# COM_R_UPDATED.net
KiCad netlist of a schematic drawn in EAGLE
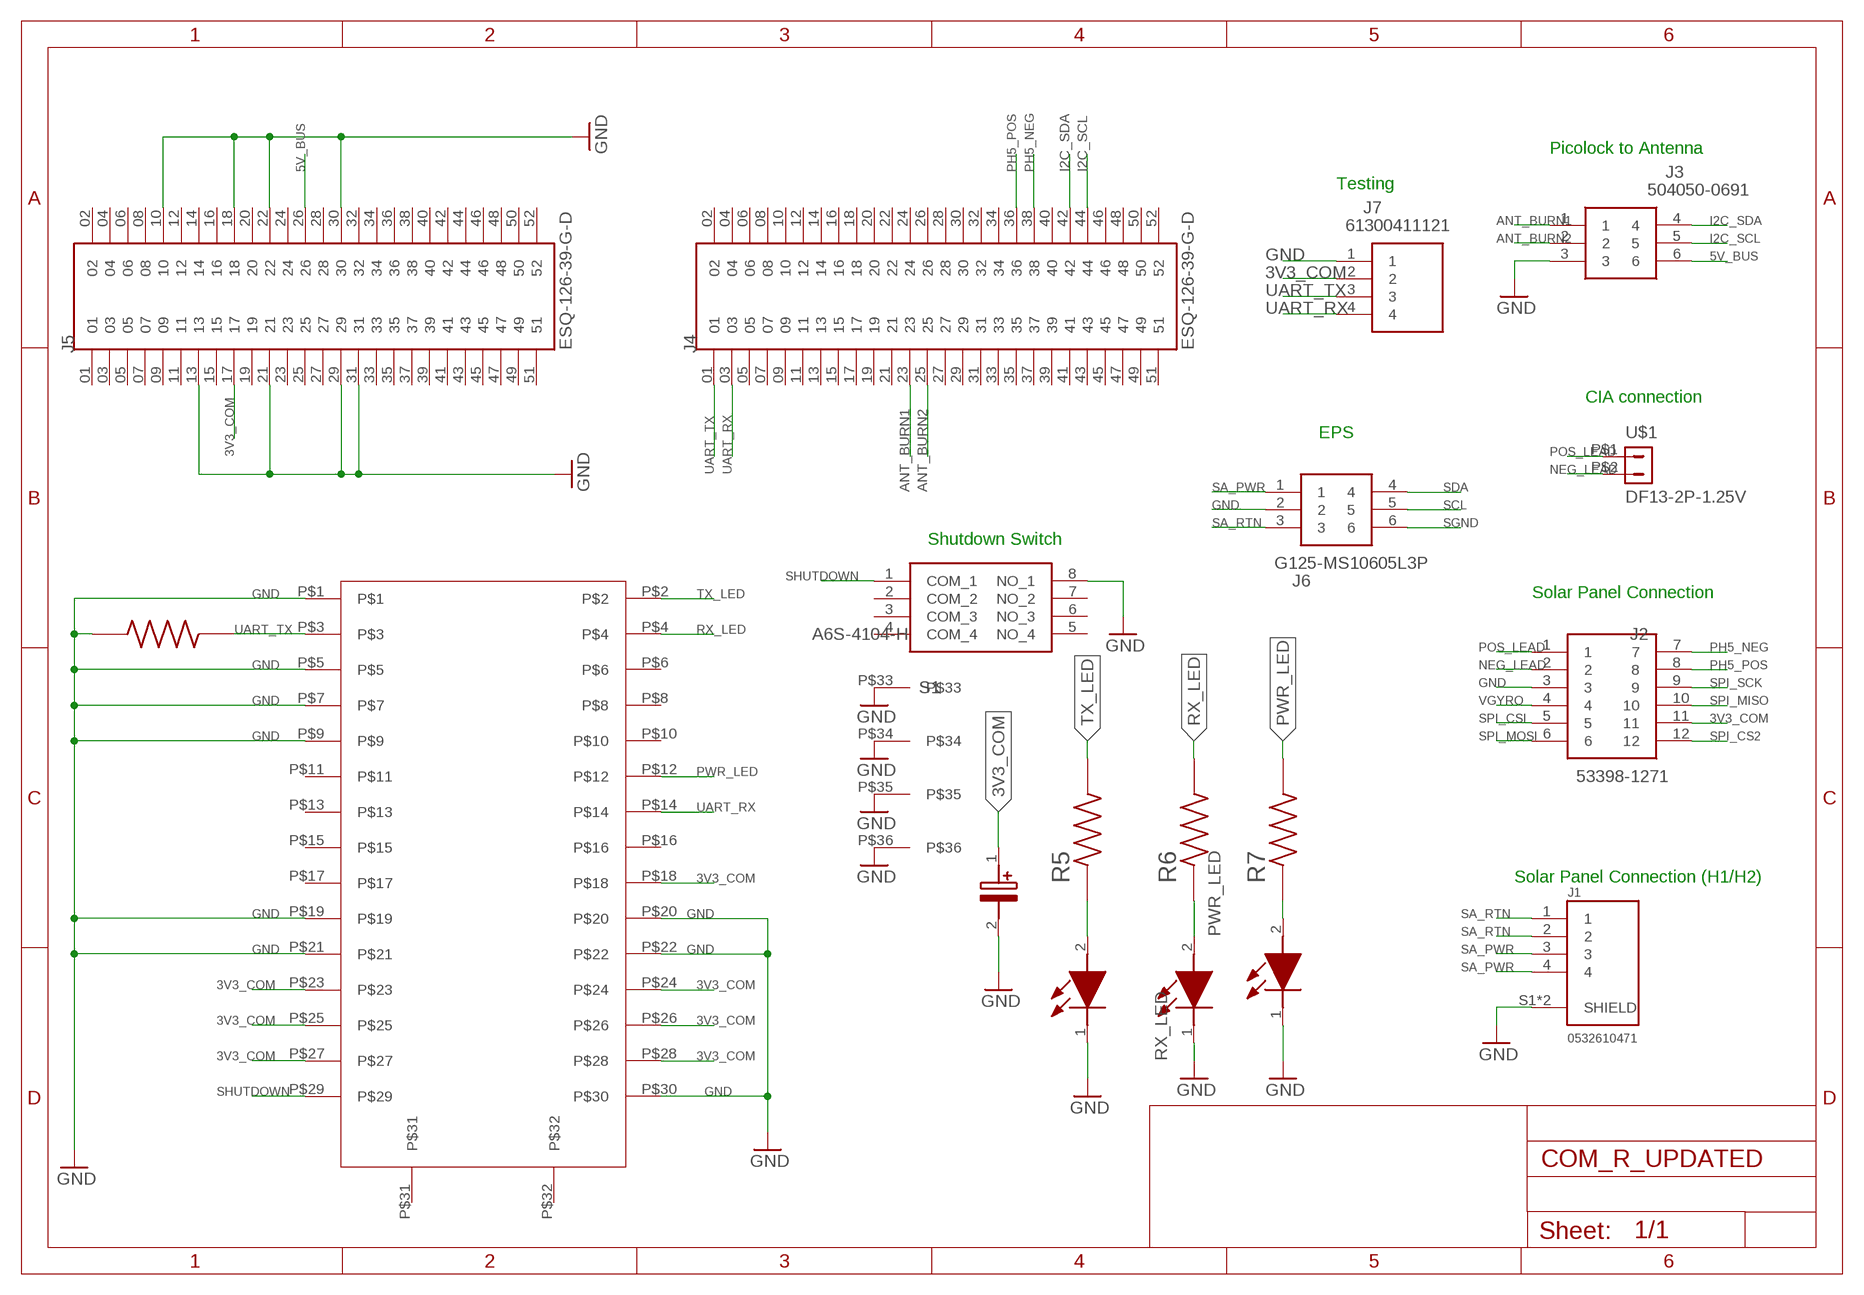
[diagram p0: schematic, sheet 1]

(export (version "E")
  (design (tool "Eeschema 10.0.6"))
  (components
    (comp (ref "C2")
      (value "293D106X0010A2TE3")
      (footprint "eagle-import:CAPPM3216X180N")
      (fields (field (name "MOUSER_PART_NUMBER") "74-293D106X0010A2TE3"))
      (libsource (lib "eagle-import") (part "293D106X0010A2TE3"))
    )
    (comp (ref "J1")
      (value "0532610471")
      (footprint "eagle-import:MOLEX_0532610471")
      (fields (field (name "MF") "Molex"))
      (libsource (lib "eagle-import") (part "0532610471"))
    )
    (comp (ref "J2")
      (value "53398-1271")
      (footprint "eagle-import:53398-1271")
      (fields (field (name "MOUSER_PART_NUMBER") "538-53398-1271"))
      (libsource (lib "eagle-import") (part "53398-1271"))
    )
    (comp (ref "J3")
      (value "504050-0691")
      (footprint "eagle-import:504050-0691_2")
      (fields (field (name "MOUSER_PART_NUMBER") "538-504050-0691"))
      (libsource (lib "eagle-import") (part "504050-0691"))
    )
    (comp (ref "J4")
      (value "ESQ-126-39-G-D")
      (footprint "eagle-import:SAMTEC_ESQ-126-39-G-D")
      (fields (field (name "MF") "Samtec"))
      (libsource (lib "eagle-import") (part "ESQ-126-39-G-D"))
    )
    (comp (ref "J5")
      (value "ESQ-126-39-G-D")
      (footprint "eagle-import:SAMTEC_ESQ-126-39-G-D")
      (fields (field (name "MF") "Samtec"))
      (libsource (lib "eagle-import") (part "ESQ-126-39-G-D"))
    )
    (comp (ref "J6")
      (value "G125-MS10605L3P")
      (footprint "eagle-import:G125-MS10605L3P")
      (fields (field (name "MOUSER_PART_NUMBER") "855-G125-MS10605L3P"))
      (libsource (lib "eagle-import") (part "G125-MS10605L3P"))
    )
    (comp (ref "J7")
      (value "61300411121")
      (footprint "eagle-import:HDRV4W95P0X254_1X4_1016X254X85")
      (fields (field (name "MOUSER_PART_NUMBER") "710-61300411121"))
      (libsource (lib "eagle-import") (part "61300411121"))
    )
    (comp (ref "PWR_LED")
      (value "HSMQ-C170-T0000")
      (footprint "eagle-import:LEDC2012X90N")
      (fields (field (name "MOUSER_PART_NUMBER") "630-HSMQ-C170-T0000"))
      (libsource (lib "eagle-import") (part "HSMQ-C170-T0000"))
    )
    (comp (ref "R3")
      (value "TNPW080510K0BETY")
      (footprint "eagle-import:RESC2012X55N")
      (fields (field (name "DIGI-KEY_PART_NUMBER") "541-3913-1-ND") (field (name "MF") "Vishay"))
      (libsource (lib "eagle-import") (part "TNPW080510K0BETY"))
    )
    (comp (ref "R5")
      (value "Y40621K00000Q0R")
      (footprint "eagle-import:RESC2012X64N")
      (fields (field (name "DIGI-KEY_PART_NUMBER") "Y4062-1.0KACT-ND") (field (name "MF") "Vishay"))
      (libsource (lib "eagle-import") (part "Y40621K00000Q0R"))
    )
    (comp (ref "R6")
      (value "Y40621K00000Q0R")
      (footprint "eagle-import:RESC2012X64N")
      (fields (field (name "DIGI-KEY_PART_NUMBER") "Y4062-1.0KACT-ND") (field (name "MF") "Vishay"))
      (libsource (lib "eagle-import") (part "Y40621K00000Q0R"))
    )
    (comp (ref "R7")
      (value "Y40621K00000Q0R")
      (footprint "eagle-import:RESC2012X64N")
      (fields (field (name "DIGI-KEY_PART_NUMBER") "Y4062-1.0KACT-ND") (field (name "MF") "Vishay"))
      (libsource (lib "eagle-import") (part "Y40621K00000Q0R"))
    )
    (comp (ref "RX_LED")
      (value "HSMQ-C170-T0000")
      (footprint "eagle-import:LEDC2012X90N")
      (fields (field (name "MOUSER_PART_NUMBER") "630-HSMQ-C170-T0000"))
      (libsource (lib "eagle-import") (part "HSMQ-C170-T0000"))
    )
    (comp (ref "S1")
      (value "A6S-4104-H")
      (footprint "eagle-import:A6S4104H")
      (fields (field (name "MOUSER_PART_NUMBER") "653-A6S-4104-H"))
      (libsource (lib "eagle-import") (part "A6S-4104-H"))
    )
    (comp (ref "TX_LED")
      (value "HSMQ-C170-T0000")
      (footprint "eagle-import:LEDC2012X90N")
      (fields (field (name "MOUSER_PART_NUMBER") "630-HSMQ-C170-T0000"))
      (libsource (lib "eagle-import") (part "HSMQ-C170-T0000"))
    )
    (comp (ref "U$1")
      (value "DF13-2P-1.25V")
      (footprint "eagle-import:DF13C-2P-1.25V")
      (libsource (lib "eagle-import") (part "DF13-2P-1.25V"))
    )
    (comp (ref "U$3")
      (value "KYOCERA_5046_30PIN")
      (footprint "eagle-import:KYOCERA_5046_30PIN")
      (libsource (lib "eagle-import") (part "KYOCERA_5046_30PIN"))
    )
  )
  (nets
    (net (code "1") (name "/5V_BUS") (class "Default")
      (node (ref "J3") (pin "6") (pinfunction "6_6") (pintype "bidirectional"))
      (node (ref "J5") (pin "26") (pinfunction "26_26") (pintype "passive"))
    )
    (net (code "2") (name "/ANT_BURN1") (class "Default")
      (node (ref "J3") (pin "1") (pinfunction "1_1") (pintype "bidirectional"))
      (node (ref "J4") (pin "23") (pinfunction "23_23") (pintype "passive"))
    )
    (net (code "3") (name "/ANT_BURN2") (class "Default")
      (node (ref "J3") (pin "2") (pinfunction "2_2") (pintype "bidirectional"))
      (node (ref "J4") (pin "25") (pinfunction "25_25") (pintype "passive"))
    )
    (net (code "4") (name "/I2C_SCL") (class "Default")
      (node (ref "J3") (pin "5") (pinfunction "5_5") (pintype "bidirectional"))
      (node (ref "J4") (pin "44") (pinfunction "44_44") (pintype "passive"))
    )
    (net (code "5") (name "/I2C_SDA") (class "Default")
      (node (ref "J3") (pin "4") (pinfunction "4_4") (pintype "bidirectional"))
      (node (ref "J4") (pin "42") (pinfunction "42_42") (pintype "passive"))
    )
    (net (code "6") (name "/NEG_LEAD") (class "Default")
      (node (ref "J2") (pin "2") (pinfunction "2_2") (pintype "bidirectional"))
      (node (ref "U$1") (pin "P$2") (pinfunction "2_P$2") (pintype "passive"))
    )
    (net (code "7") (name "/PH5_NEG") (class "Default")
      (node (ref "J2") (pin "7") (pinfunction "7_7") (pintype "bidirectional"))
      (node (ref "J4") (pin "38") (pinfunction "38_38") (pintype "passive"))
    )
    (net (code "8") (name "/PH5_POS") (class "Default")
      (node (ref "J2") (pin "8") (pinfunction "8_8") (pintype "bidirectional"))
      (node (ref "J4") (pin "36") (pinfunction "36_36") (pintype "passive"))
    )
    (net (code "9") (name "/POS_LEAD") (class "Default")
      (node (ref "J2") (pin "1") (pinfunction "1_1") (pintype "bidirectional"))
      (node (ref "U$1") (pin "P$1") (pinfunction "1_P$1") (pintype "passive"))
    )
    (net (code "10") (name "/SA_PWR") (class "Default")
      (node (ref "J1") (pin "3") (pinfunction "3_3") (pintype "passive"))
      (node (ref "J1") (pin "4") (pinfunction "4_4") (pintype "passive"))
      (node (ref "J6") (pin "1") (pinfunction "1_1") (pintype "bidirectional"))
    )
    (net (code "11") (name "/SA_RTN") (class "Default")
      (node (ref "J1") (pin "1") (pinfunction "1_1") (pintype "passive"))
      (node (ref "J1") (pin "2") (pinfunction "2_2") (pintype "passive"))
      (node (ref "J6") (pin "3") (pinfunction "3_3") (pintype "bidirectional"))
    )
    (net (code "12") (name "/SCL") (class "Default")
      (node (ref "J6") (pin "5") (pinfunction "5_5") (pintype "bidirectional"))
    )
    (net (code "13") (name "/SDA") (class "Default")
      (node (ref "J6") (pin "4") (pinfunction "4_4") (pintype "bidirectional"))
    )
    (net (code "14") (name "/SGND") (class "Default")
      (node (ref "J6") (pin "6") (pinfunction "6_6") (pintype "bidirectional"))
    )
    (net (code "15") (name "/SHUTDOWN") (class "Default")
      (node (ref "S1") (pin "1") (pinfunction "COM_1_1") (pintype "bidirectional"))
      (node (ref "U$3") (pin "P$29") (pinfunction "P$29_P$29") (pintype "bidirectional"))
    )
    (net (code "16") (name "/SPI_CS2") (class "Default")
      (node (ref "J2") (pin "12") (pinfunction "12_12") (pintype "bidirectional"))
    )
    (net (code "17") (name "/SPI_CSI") (class "Default")
      (node (ref "J2") (pin "5") (pinfunction "5_5") (pintype "bidirectional"))
    )
    (net (code "18") (name "/SPI_MISO") (class "Default")
      (node (ref "J2") (pin "10") (pinfunction "10_10") (pintype "bidirectional"))
    )
    (net (code "19") (name "/SPI_MOSI") (class "Default")
      (node (ref "J2") (pin "6") (pinfunction "6_6") (pintype "bidirectional"))
    )
    (net (code "20") (name "/SPI_SCK") (class "Default")
      (node (ref "J2") (pin "9") (pinfunction "9_9") (pintype "bidirectional"))
    )
    (net (code "21") (name "/UART_RX") (class "Default")
      (node (ref "J4") (pin "03") (pinfunction "03_03") (pintype "passive"))
      (node (ref "J7") (pin "4") (pinfunction "4_4") (pintype "bidirectional"))
      (node (ref "U$3") (pin "P$14") (pinfunction "P$14_P$14") (pintype "bidirectional"))
    )
    (net (code "22") (name "/UART_TX") (class "Default")
      (node (ref "J4") (pin "01") (pinfunction "01_01") (pintype "passive"))
      (node (ref "J7") (pin "3") (pinfunction "3_3") (pintype "bidirectional"))
      (node (ref "R3") (pin "2") (pinfunction "2_2") (pintype "passive"))
      (node (ref "U$3") (pin "P$3") (pinfunction "P$3_P$3") (pintype "bidirectional"))
    )
    (net (code "23") (name "/VGYRO") (class "Default")
      (node (ref "J2") (pin "4") (pinfunction "4_4") (pintype "bidirectional"))
    )
    (net (code "24") (name "3V3_COM") (class "Default")
      (node (ref "C2") (pin "1") (pinfunction "+_1") (pintype "bidirectional"))
      (node (ref "J2") (pin "11") (pinfunction "11_11") (pintype "bidirectional"))
      (node (ref "J5") (pin "17") (pinfunction "17_17") (pintype "passive"))
      (node (ref "J7") (pin "2") (pinfunction "2_2") (pintype "bidirectional"))
      (node (ref "U$3") (pin "P$18") (pinfunction "P$18_P$18") (pintype "bidirectional"))
      (node (ref "U$3") (pin "P$23") (pinfunction "P$23_P$23") (pintype "bidirectional"))
      (node (ref "U$3") (pin "P$24") (pinfunction "P$24_P$24") (pintype "bidirectional"))
      (node (ref "U$3") (pin "P$25") (pinfunction "P$25_P$25") (pintype "bidirectional"))
      (node (ref "U$3") (pin "P$26") (pinfunction "P$26_P$26") (pintype "bidirectional"))
      (node (ref "U$3") (pin "P$27") (pinfunction "P$27_P$27") (pintype "bidirectional"))
      (node (ref "U$3") (pin "P$28") (pinfunction "P$28_P$28") (pintype "bidirectional"))
    )
    (net (code "25") (name "GND") (class "Default")
      (node (ref "C2") (pin "2") (pinfunction "-_2") (pintype "bidirectional"))
      (node (ref "J1") (pin "S1") (pinfunction "SHIELD_S1") (pintype "passive"))
      (node (ref "J1") (pin "S2") (pinfunction "SHIELD_S2") (pintype "passive"))
      (node (ref "J2") (pin "3") (pinfunction "3_3") (pintype "bidirectional"))
      (node (ref "J3") (pin "3") (pinfunction "3_3") (pintype "bidirectional"))
      (node (ref "J5") (pin "10") (pinfunction "10_10") (pintype "passive"))
      (node (ref "J5") (pin "13") (pinfunction "13_13") (pintype "passive"))
      (node (ref "J5") (pin "18") (pinfunction "18_18") (pintype "passive"))
      (node (ref "J5") (pin "21") (pinfunction "21_21") (pintype "passive"))
      (node (ref "J5") (pin "22") (pinfunction "22_22") (pintype "passive"))
      (node (ref "J5") (pin "29") (pinfunction "29_29") (pintype "passive"))
      (node (ref "J5") (pin "30") (pinfunction "30_30") (pintype "passive"))
      (node (ref "J5") (pin "31") (pinfunction "31_31") (pintype "passive"))
      (node (ref "J6") (pin "2") (pinfunction "2_2") (pintype "bidirectional"))
      (node (ref "J7") (pin "1") (pinfunction "1_1") (pintype "bidirectional"))
      (node (ref "PWR_LED") (pin "1") (pinfunction "K_1") (pintype "bidirectional"))
      (node (ref "R3") (pin "1") (pinfunction "1_1") (pintype "passive"))
      (node (ref "RX_LED") (pin "1") (pinfunction "K_1") (pintype "bidirectional"))
      (node (ref "S1") (pin "8") (pinfunction "NO_1_8") (pintype "bidirectional"))
      (node (ref "TX_LED") (pin "1") (pinfunction "K_1") (pintype "bidirectional"))
      (node (ref "U$3") (pin "P$1") (pinfunction "P$1_P$1") (pintype "bidirectional"))
      (node (ref "U$3") (pin "P$19") (pinfunction "P$19_P$19") (pintype "bidirectional"))
      (node (ref "U$3") (pin "P$20") (pinfunction "P$20_P$20") (pintype "bidirectional"))
      (node (ref "U$3") (pin "P$21") (pinfunction "P$21_P$21") (pintype "bidirectional"))
      (node (ref "U$3") (pin "P$22") (pinfunction "P$22_P$22") (pintype "bidirectional"))
      (node (ref "U$3") (pin "P$30") (pinfunction "P$30_P$30") (pintype "bidirectional"))
      (node (ref "U$3") (pin "P$33") (pinfunction "P$33_P$33") (pintype "bidirectional"))
      (node (ref "U$3") (pin "P$34") (pinfunction "P$34_P$34") (pintype "bidirectional"))
      (node (ref "U$3") (pin "P$35") (pinfunction "P$35_P$35") (pintype "bidirectional"))
      (node (ref "U$3") (pin "P$36") (pinfunction "P$36_P$36") (pintype "bidirectional"))
      (node (ref "U$3") (pin "P$5") (pinfunction "P$5_P$5") (pintype "bidirectional"))
      (node (ref "U$3") (pin "P$7") (pinfunction "P$7_P$7") (pintype "bidirectional"))
      (node (ref "U$3") (pin "P$9") (pinfunction "P$9_P$9") (pintype "bidirectional"))
    )
    (net (code "26") (name "Net-(PWR_LED-A)") (class "Default")
      (node (ref "PWR_LED") (pin "2") (pinfunction "A_2") (pintype "bidirectional"))
      (node (ref "R7") (pin "1") (pinfunction "1_1") (pintype "passive"))
    )
    (net (code "27") (name "Net-(RX_LED-A)") (class "Default")
      (node (ref "R6") (pin "1") (pinfunction "1_1") (pintype "passive"))
      (node (ref "RX_LED") (pin "2") (pinfunction "A_2") (pintype "bidirectional"))
    )
    (net (code "28") (name "Net-(TX_LED-A)") (class "Default")
      (node (ref "R5") (pin "1") (pinfunction "1_1") (pintype "passive"))
      (node (ref "TX_LED") (pin "2") (pinfunction "A_2") (pintype "bidirectional"))
    )
    (net (code "29") (name "PWR_LED") (class "Default")
      (node (ref "R7") (pin "2") (pinfunction "2_2") (pintype "passive"))
      (node (ref "U$3") (pin "P$12") (pinfunction "P$12_P$12") (pintype "bidirectional"))
    )
    (net (code "30") (name "RX_LED") (class "Default")
      (node (ref "R6") (pin "2") (pinfunction "2_2") (pintype "passive"))
      (node (ref "U$3") (pin "P$4") (pinfunction "P$4_P$4") (pintype "bidirectional"))
    )
    (net (code "31") (name "TX_LED") (class "Default")
      (node (ref "R5") (pin "2") (pinfunction "2_2") (pintype "passive"))
      (node (ref "U$3") (pin "P$2") (pinfunction "P$2_P$2") (pintype "bidirectional"))
    )
    (net (code "32") (name "unconnected-(J4-Pad02)") (class "Default")
      (node (ref "J4") (pin "02") (pinfunction "02_02") (pintype "passive"))
    )
    (net (code "33") (name "unconnected-(J4-Pad04)") (class "Default")
      (node (ref "J4") (pin "04") (pinfunction "04_04") (pintype "passive"))
    )
    (net (code "34") (name "unconnected-(J4-Pad05)") (class "Default")
      (node (ref "J4") (pin "05") (pinfunction "05_05") (pintype "passive"))
    )
    (net (code "35") (name "unconnected-(J4-Pad06)") (class "Default")
      (node (ref "J4") (pin "06") (pinfunction "06_06") (pintype "passive"))
    )
    (net (code "36") (name "unconnected-(J4-Pad07)") (class "Default")
      (node (ref "J4") (pin "07") (pinfunction "07_07") (pintype "passive"))
    )
    (net (code "37") (name "unconnected-(J4-Pad08)") (class "Default")
      (node (ref "J4") (pin "08") (pinfunction "08_08") (pintype "passive"))
    )
    (net (code "38") (name "unconnected-(J4-Pad09)") (class "Default")
      (node (ref "J4") (pin "09") (pinfunction "09_09") (pintype "passive"))
    )
    (net (code "39") (name "unconnected-(J4-Pad10)") (class "Default")
      (node (ref "J4") (pin "10") (pinfunction "10_10") (pintype "passive"))
    )
    (net (code "40") (name "unconnected-(J4-Pad11)") (class "Default")
      (node (ref "J4") (pin "11") (pinfunction "11_11") (pintype "passive"))
    )
    (net (code "41") (name "unconnected-(J4-Pad12)") (class "Default")
      (node (ref "J4") (pin "12") (pinfunction "12_12") (pintype "passive"))
    )
    (net (code "42") (name "unconnected-(J4-Pad13)") (class "Default")
      (node (ref "J4") (pin "13") (pinfunction "13_13") (pintype "passive"))
    )
    (net (code "43") (name "unconnected-(J4-Pad14)") (class "Default")
      (node (ref "J4") (pin "14") (pinfunction "14_14") (pintype "passive"))
    )
    (net (code "44") (name "unconnected-(J4-Pad15)") (class "Default")
      (node (ref "J4") (pin "15") (pinfunction "15_15") (pintype "passive"))
    )
    (net (code "45") (name "unconnected-(J4-Pad16)") (class "Default")
      (node (ref "J4") (pin "16") (pinfunction "16_16") (pintype "passive"))
    )
    (net (code "46") (name "unconnected-(J4-Pad17)") (class "Default")
      (node (ref "J4") (pin "17") (pinfunction "17_17") (pintype "passive"))
    )
    (net (code "47") (name "unconnected-(J4-Pad18)") (class "Default")
      (node (ref "J4") (pin "18") (pinfunction "18_18") (pintype "passive"))
    )
    (net (code "48") (name "unconnected-(J4-Pad19)") (class "Default")
      (node (ref "J4") (pin "19") (pinfunction "19_19") (pintype "passive"))
    )
    (net (code "49") (name "unconnected-(J4-Pad20)") (class "Default")
      (node (ref "J4") (pin "20") (pinfunction "20_20") (pintype "passive"))
    )
    (net (code "50") (name "unconnected-(J4-Pad21)") (class "Default")
      (node (ref "J4") (pin "21") (pinfunction "21_21") (pintype "passive"))
    )
    (net (code "51") (name "unconnected-(J4-Pad22)") (class "Default")
      (node (ref "J4") (pin "22") (pinfunction "22_22") (pintype "passive"))
    )
    (net (code "52") (name "unconnected-(J4-Pad24)") (class "Default")
      (node (ref "J4") (pin "24") (pinfunction "24_24") (pintype "passive"))
    )
    (net (code "53") (name "unconnected-(J4-Pad26)") (class "Default")
      (node (ref "J4") (pin "26") (pinfunction "26_26") (pintype "passive"))
    )
    (net (code "54") (name "unconnected-(J4-Pad27)") (class "Default")
      (node (ref "J4") (pin "27") (pinfunction "27_27") (pintype "passive"))
    )
    (net (code "55") (name "unconnected-(J4-Pad28)") (class "Default")
      (node (ref "J4") (pin "28") (pinfunction "28_28") (pintype "passive"))
    )
    (net (code "56") (name "unconnected-(J4-Pad29)") (class "Default")
      (node (ref "J4") (pin "29") (pinfunction "29_29") (pintype "passive"))
    )
    (net (code "57") (name "unconnected-(J4-Pad30)") (class "Default")
      (node (ref "J4") (pin "30") (pinfunction "30_30") (pintype "passive"))
    )
    (net (code "58") (name "unconnected-(J4-Pad31)") (class "Default")
      (node (ref "J4") (pin "31") (pinfunction "31_31") (pintype "passive"))
    )
    (net (code "59") (name "unconnected-(J4-Pad32)") (class "Default")
      (node (ref "J4") (pin "32") (pinfunction "32_32") (pintype "passive"))
    )
    (net (code "60") (name "unconnected-(J4-Pad33)") (class "Default")
      (node (ref "J4") (pin "33") (pinfunction "33_33") (pintype "passive"))
    )
    (net (code "61") (name "unconnected-(J4-Pad34)") (class "Default")
      (node (ref "J4") (pin "34") (pinfunction "34_34") (pintype "passive"))
    )
    (net (code "62") (name "unconnected-(J4-Pad35)") (class "Default")
      (node (ref "J4") (pin "35") (pinfunction "35_35") (pintype "passive"))
    )
    (net (code "63") (name "unconnected-(J4-Pad37)") (class "Default")
      (node (ref "J4") (pin "37") (pinfunction "37_37") (pintype "passive"))
    )
    (net (code "64") (name "unconnected-(J4-Pad39)") (class "Default")
      (node (ref "J4") (pin "39") (pinfunction "39_39") (pintype "passive"))
    )
    (net (code "65") (name "unconnected-(J4-Pad40)") (class "Default")
      (node (ref "J4") (pin "40") (pinfunction "40_40") (pintype "passive"))
    )
    (net (code "66") (name "unconnected-(J4-Pad41)") (class "Default")
      (node (ref "J4") (pin "41") (pinfunction "41_41") (pintype "passive"))
    )
    (net (code "67") (name "unconnected-(J4-Pad43)") (class "Default")
      (node (ref "J4") (pin "43") (pinfunction "43_43") (pintype "passive"))
    )
    (net (code "68") (name "unconnected-(J4-Pad45)") (class "Default")
      (node (ref "J4") (pin "45") (pinfunction "45_45") (pintype "passive"))
    )
    (net (code "69") (name "unconnected-(J4-Pad46)") (class "Default")
      (node (ref "J4") (pin "46") (pinfunction "46_46") (pintype "passive"))
    )
    (net (code "70") (name "unconnected-(J4-Pad47)") (class "Default")
      (node (ref "J4") (pin "47") (pinfunction "47_47") (pintype "passive"))
    )
    (net (code "71") (name "unconnected-(J4-Pad48)") (class "Default")
      (node (ref "J4") (pin "48") (pinfunction "48_48") (pintype "passive"))
    )
    (net (code "72") (name "unconnected-(J4-Pad49)") (class "Default")
      (node (ref "J4") (pin "49") (pinfunction "49_49") (pintype "passive"))
    )
    (net (code "73") (name "unconnected-(J4-Pad50)") (class "Default")
      (node (ref "J4") (pin "50") (pinfunction "50_50") (pintype "passive"))
    )
    (net (code "74") (name "unconnected-(J4-Pad51)") (class "Default")
      (node (ref "J4") (pin "51") (pinfunction "51_51") (pintype "passive"))
    )
    (net (code "75") (name "unconnected-(J4-Pad52)") (class "Default")
      (node (ref "J4") (pin "52") (pinfunction "52_52") (pintype "passive"))
    )
    (net (code "76") (name "unconnected-(J5-Pad01)") (class "Default")
      (node (ref "J5") (pin "01") (pinfunction "01_01") (pintype "passive"))
    )
    (net (code "77") (name "unconnected-(J5-Pad02)") (class "Default")
      (node (ref "J5") (pin "02") (pinfunction "02_02") (pintype "passive"))
    )
    (net (code "78") (name "unconnected-(J5-Pad03)") (class "Default")
      (node (ref "J5") (pin "03") (pinfunction "03_03") (pintype "passive"))
    )
    (net (code "79") (name "unconnected-(J5-Pad04)") (class "Default")
      (node (ref "J5") (pin "04") (pinfunction "04_04") (pintype "passive"))
    )
    (net (code "80") (name "unconnected-(J5-Pad05)") (class "Default")
      (node (ref "J5") (pin "05") (pinfunction "05_05") (pintype "passive"))
    )
    (net (code "81") (name "unconnected-(J5-Pad06)") (class "Default")
      (node (ref "J5") (pin "06") (pinfunction "06_06") (pintype "passive"))
    )
    (net (code "82") (name "unconnected-(J5-Pad07)") (class "Default")
      (node (ref "J5") (pin "07") (pinfunction "07_07") (pintype "passive"))
    )
    (net (code "83") (name "unconnected-(J5-Pad08)") (class "Default")
      (node (ref "J5") (pin "08") (pinfunction "08_08") (pintype "passive"))
    )
    (net (code "84") (name "unconnected-(J5-Pad09)") (class "Default")
      (node (ref "J5") (pin "09") (pinfunction "09_09") (pintype "passive"))
    )
    (net (code "85") (name "unconnected-(J5-Pad11)") (class "Default")
      (node (ref "J5") (pin "11") (pinfunction "11_11") (pintype "passive"))
    )
    (net (code "86") (name "unconnected-(J5-Pad12)") (class "Default")
      (node (ref "J5") (pin "12") (pinfunction "12_12") (pintype "passive"))
    )
    (net (code "87") (name "unconnected-(J5-Pad14)") (class "Default")
      (node (ref "J5") (pin "14") (pinfunction "14_14") (pintype "passive"))
    )
    (net (code "88") (name "unconnected-(J5-Pad15)") (class "Default")
      (node (ref "J5") (pin "15") (pinfunction "15_15") (pintype "passive"))
    )
    (net (code "89") (name "unconnected-(J5-Pad16)") (class "Default")
      (node (ref "J5") (pin "16") (pinfunction "16_16") (pintype "passive"))
    )
    (net (code "90") (name "unconnected-(J5-Pad19)") (class "Default")
      (node (ref "J5") (pin "19") (pinfunction "19_19") (pintype "passive"))
    )
    (net (code "91") (name "unconnected-(J5-Pad20)") (class "Default")
      (node (ref "J5") (pin "20") (pinfunction "20_20") (pintype "passive"))
    )
    (net (code "92") (name "unconnected-(J5-Pad23)") (class "Default")
      (node (ref "J5") (pin "23") (pinfunction "23_23") (pintype "passive"))
    )
    (net (code "93") (name "unconnected-(J5-Pad24)") (class "Default")
      (node (ref "J5") (pin "24") (pinfunction "24_24") (pintype "passive"))
    )
    (net (code "94") (name "unconnected-(J5-Pad25)") (class "Default")
      (node (ref "J5") (pin "25") (pinfunction "25_25") (pintype "passive"))
    )
    (net (code "95") (name "unconnected-(J5-Pad27)") (class "Default")
      (node (ref "J5") (pin "27") (pinfunction "27_27") (pintype "passive"))
    )
    (net (code "96") (name "unconnected-(J5-Pad28)") (class "Default")
      (node (ref "J5") (pin "28") (pinfunction "28_28") (pintype "passive"))
    )
    (net (code "97") (name "unconnected-(J5-Pad32)") (class "Default")
      (node (ref "J5") (pin "32") (pinfunction "32_32") (pintype "passive"))
    )
    (net (code "98") (name "unconnected-(J5-Pad33)") (class "Default")
      (node (ref "J5") (pin "33") (pinfunction "33_33") (pintype "passive"))
    )
    (net (code "99") (name "unconnected-(J5-Pad34)") (class "Default")
      (node (ref "J5") (pin "34") (pinfunction "34_34") (pintype "passive"))
    )
    (net (code "100") (name "unconnected-(J5-Pad35)") (class "Default")
      (node (ref "J5") (pin "35") (pinfunction "35_35") (pintype "passive"))
    )
    (net (code "101") (name "unconnected-(J5-Pad36)") (class "Default")
      (node (ref "J5") (pin "36") (pinfunction "36_36") (pintype "passive"))
    )
    (net (code "102") (name "unconnected-(J5-Pad37)") (class "Default")
      (node (ref "J5") (pin "37") (pinfunction "37_37") (pintype "passive"))
    )
    (net (code "103") (name "unconnected-(J5-Pad38)") (class "Default")
      (node (ref "J5") (pin "38") (pinfunction "38_38") (pintype "passive"))
    )
    (net (code "104") (name "unconnected-(J5-Pad39)") (class "Default")
      (node (ref "J5") (pin "39") (pinfunction "39_39") (pintype "passive"))
    )
    (net (code "105") (name "unconnected-(J5-Pad40)") (class "Default")
      (node (ref "J5") (pin "40") (pinfunction "40_40") (pintype "passive"))
    )
    (net (code "106") (name "unconnected-(J5-Pad41)") (class "Default")
      (node (ref "J5") (pin "41") (pinfunction "41_41") (pintype "passive"))
    )
    (net (code "107") (name "unconnected-(J5-Pad42)") (class "Default")
      (node (ref "J5") (pin "42") (pinfunction "42_42") (pintype "passive"))
    )
    (net (code "108") (name "unconnected-(J5-Pad43)") (class "Default")
      (node (ref "J5") (pin "43") (pinfunction "43_43") (pintype "passive"))
    )
    (net (code "109") (name "unconnected-(J5-Pad44)") (class "Default")
      (node (ref "J5") (pin "44") (pinfunction "44_44") (pintype "passive"))
    )
    (net (code "110") (name "unconnected-(J5-Pad45)") (class "Default")
      (node (ref "J5") (pin "45") (pinfunction "45_45") (pintype "passive"))
    )
    (net (code "111") (name "unconnected-(J5-Pad46)") (class "Default")
      (node (ref "J5") (pin "46") (pinfunction "46_46") (pintype "passive"))
    )
    (net (code "112") (name "unconnected-(J5-Pad47)") (class "Default")
      (node (ref "J5") (pin "47") (pinfunction "47_47") (pintype "passive"))
    )
    (net (code "113") (name "unconnected-(J5-Pad48)") (class "Default")
      (node (ref "J5") (pin "48") (pinfunction "48_48") (pintype "passive"))
    )
    (net (code "114") (name "unconnected-(J5-Pad49)") (class "Default")
      (node (ref "J5") (pin "49") (pinfunction "49_49") (pintype "passive"))
    )
    (net (code "115") (name "unconnected-(J5-Pad50)") (class "Default")
      (node (ref "J5") (pin "50") (pinfunction "50_50") (pintype "passive"))
    )
    (net (code "116") (name "unconnected-(J5-Pad51)") (class "Default")
      (node (ref "J5") (pin "51") (pinfunction "51_51") (pintype "passive"))
    )
    (net (code "117") (name "unconnected-(J5-Pad52)") (class "Default")
      (node (ref "J5") (pin "52") (pinfunction "52_52") (pintype "passive"))
    )
    (net (code "118") (name "unconnected-(S1-COM_2-Pad2)") (class "Default")
      (node (ref "S1") (pin "2") (pinfunction "COM_2_2") (pintype "bidirectional"))
    )
    (net (code "119") (name "unconnected-(S1-COM_3-Pad3)") (class "Default")
      (node (ref "S1") (pin "3") (pinfunction "COM_3_3") (pintype "bidirectional"))
    )
    (net (code "120") (name "unconnected-(S1-COM_4-Pad4)") (class "Default")
      (node (ref "S1") (pin "4") (pinfunction "COM_4_4") (pintype "bidirectional"))
    )
    (net (code "121") (name "unconnected-(S1-NO_2-Pad7)") (class "Default")
      (node (ref "S1") (pin "7") (pinfunction "NO_2_7") (pintype "bidirectional"))
    )
    (net (code "122") (name "unconnected-(S1-NO_3-Pad6)") (class "Default")
      (node (ref "S1") (pin "6") (pinfunction "NO_3_6") (pintype "bidirectional"))
    )
    (net (code "123") (name "unconnected-(S1-NO_4-Pad5)") (class "Default")
      (node (ref "S1") (pin "5") (pinfunction "NO_4_5") (pintype "bidirectional"))
    )
    (net (code "124") (name "unconnected-(U$3-PadP$6)") (class "Default")
      (node (ref "U$3") (pin "P$6") (pinfunction "P$6_P$6") (pintype "bidirectional"))
    )
    (net (code "125") (name "unconnected-(U$3-PadP$8)") (class "Default")
      (node (ref "U$3") (pin "P$8") (pinfunction "P$8_P$8") (pintype "bidirectional"))
    )
    (net (code "126") (name "unconnected-(U$3-PadP$10)") (class "Default")
      (node (ref "U$3") (pin "P$10") (pinfunction "P$10_P$10") (pintype "bidirectional"))
    )
    (net (code "127") (name "unconnected-(U$3-PadP$11)") (class "Default")
      (node (ref "U$3") (pin "P$11") (pinfunction "P$11_P$11") (pintype "bidirectional"))
    )
    (net (code "128") (name "unconnected-(U$3-PadP$13)") (class "Default")
      (node (ref "U$3") (pin "P$13") (pinfunction "P$13_P$13") (pintype "bidirectional"))
    )
    (net (code "129") (name "unconnected-(U$3-PadP$15)") (class "Default")
      (node (ref "U$3") (pin "P$15") (pinfunction "P$15_P$15") (pintype "bidirectional"))
    )
    (net (code "130") (name "unconnected-(U$3-PadP$16)") (class "Default")
      (node (ref "U$3") (pin "P$16") (pinfunction "P$16_P$16") (pintype "bidirectional"))
    )
    (net (code "131") (name "unconnected-(U$3-PadP$17)") (class "Default")
      (node (ref "U$3") (pin "P$17") (pinfunction "P$17_P$17") (pintype "bidirectional"))
    )
    (net (code "132") (name "unconnected-(U$3-PadP$31)") (class "Default")
      (node (ref "U$3") (pin "P$31") (pinfunction "P$31_P$31") (pintype "bidirectional"))
    )
    (net (code "133") (name "unconnected-(U$3-PadP$32)") (class "Default")
      (node (ref "U$3") (pin "P$32") (pinfunction "P$32_P$32") (pintype "bidirectional"))
    )
  )
)
